# coil_processing.net
KiCad netlist of a schematic drawn in Altium Designer
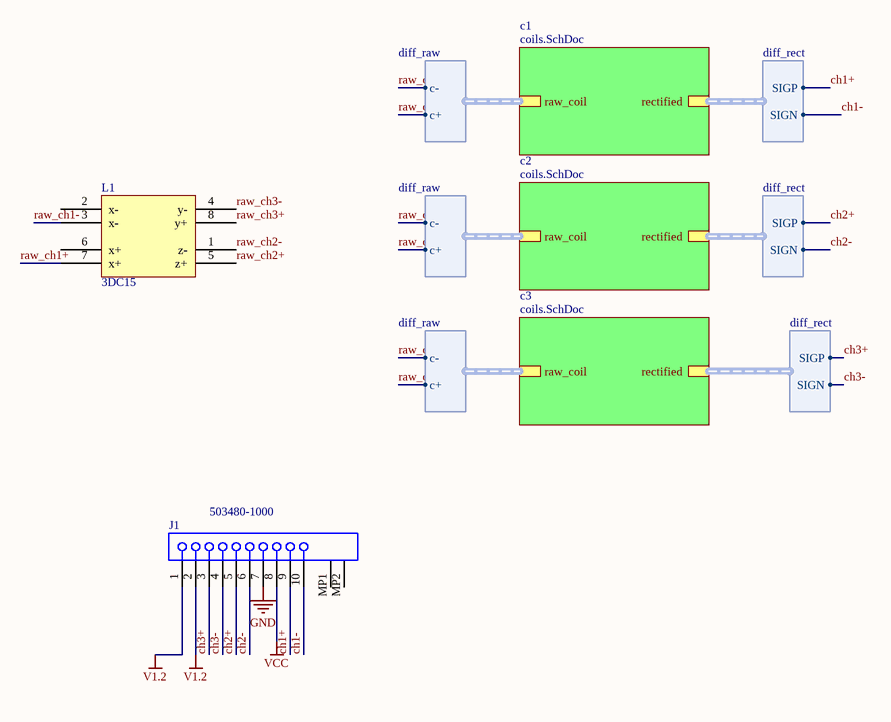
[diagram p0: coil_processing.SchDoc]

(export (version "E")
  (design (tool "Eeschema 10.0.6"))
  (components
    (comp (ref "J1")
      (value "503480-1000")
      (footprint "MOLX-503480-1000")
      (fields (field (name "MANUFACTURER") "Molex"))
      (libsource (lib "Altium Content Vault") (part "MOLX-503480-1000"))
    )
    (comp (ref "L1") (value "3DC15") (footprint "3DC15") (libsource (lib "maglib") (part "3DV09-A")))
  )
  (nets
    (net (code "3") (name "/ch1+") (class "Default")
      (node (ref "J1") (pin "9") (pinfunction "9_9") (pintype "passive"))
    )
    (net (code "4") (name "/ch1-") (class "Default")
      (node (ref "J1") (pin "10") (pinfunction "10_10") (pintype "passive"))
    )
    (net (code "5") (name "/ch2+") (class "Default")
      (node (ref "J1") (pin "5") (pinfunction "5_5") (pintype "passive"))
    )
    (net (code "6") (name "/ch2-") (class "Default")
      (node (ref "J1") (pin "6") (pinfunction "6_6") (pintype "passive"))
    )
    (net (code "7") (name "/ch3+") (class "Default")
      (node (ref "J1") (pin "3") (pinfunction "3_3") (pintype "passive"))
    )
    (net (code "8") (name "/ch3-") (class "Default")
      (node (ref "J1") (pin "4") (pinfunction "4_4") (pintype "passive"))
    )
    (net (code "9") (name "/raw_ch1+") (class "Default")
      (node (ref "L1") (pin "7") (pinfunction "x+_7") (pintype "passive"))
    )
    (net (code "10") (name "/raw_ch1-") (class "Default")
      (node (ref "L1") (pin "3") (pinfunction "x-_3") (pintype "passive"))
    )
    (net (code "11") (name "/raw_ch2+") (class "Default")
      (node (ref "L1") (pin "5") (pinfunction "z+_5") (pintype "passive"))
    )
    (net (code "12") (name "/raw_ch2-") (class "Default")
      (node (ref "L1") (pin "1") (pinfunction "z-_1") (pintype "passive"))
    )
    (net (code "13") (name "/raw_ch3+") (class "Default")
      (node (ref "L1") (pin "8") (pinfunction "y+_8") (pintype "passive"))
    )
    (net (code "14") (name "/raw_ch3-") (class "Default")
      (node (ref "L1") (pin "4") (pinfunction "y-_4") (pintype "passive"))
    )
    (net (code "17") (name "GND") (class "Default")
      (node (ref "J1") (pin "7") (pinfunction "7_7") (pintype "passive"))
    )
    (net (code "18") (name "V1.2") (class "Default")
      (node (ref "J1") (pin "1") (pinfunction "1_1") (pintype "passive"))
      (node (ref "J1") (pin "2") (pinfunction "2_2") (pintype "passive"))
    )
    (net (code "19") (name "VCC") (class "Default")
      (node (ref "J1") (pin "8") (pinfunction "8_8") (pintype "passive"))
    )
    (net (code "20") (name "unconnected-(J1-PadMP1)") (class "Default")
      (node (ref "J1") (pin "MP1") (pinfunction "MP1_MP1") (pintype "passive"))
    )
    (net (code "21") (name "unconnected-(J1-PadMP2)") (class "Default")
      (node (ref "J1") (pin "MP2") (pinfunction "MP2_MP2") (pintype "passive"))
    )
    (net (code "22") (name "unconnected-(L1-x+-Pad6)") (class "Default")
      (node (ref "L1") (pin "6") (pinfunction "x+_6") (pintype "passive"))
    )
    (net (code "23") (name "unconnected-(L1-x--Pad2)") (class "Default")
      (node (ref "L1") (pin "2") (pinfunction "x-_2") (pintype "passive"))
    )
  )
)
